# esp32_drone.net
KiCad netlist of a schematic drawn in EAGLE
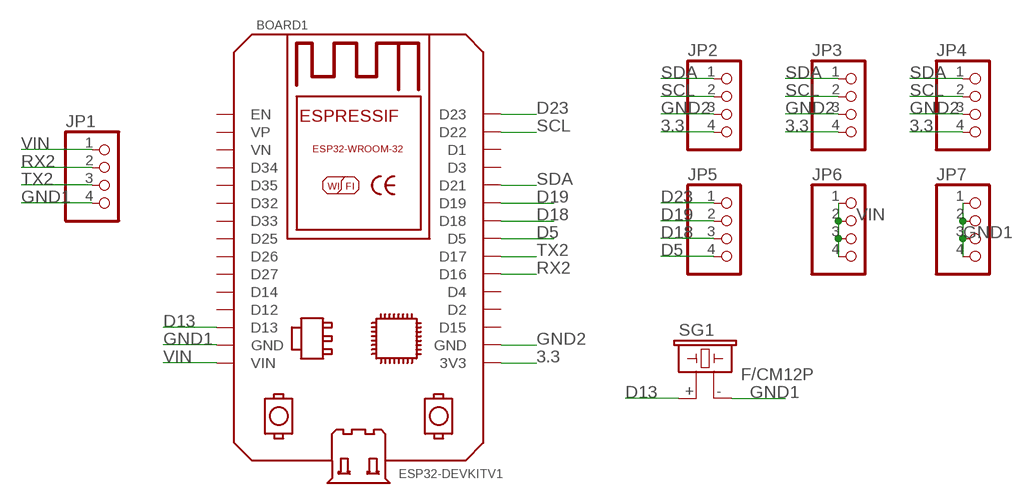
[diagram p0: schematic, sheet 1]

(export (version "E")
  (design (tool "Eeschema 10.0.6"))
  (components
    (comp (ref "BOARD1")
      (value "ESP32DEVKITV1")
      (footprint "eagle-import:ESP32-DEVKITV1")
      (libsource (lib "eagle-import") (part "ESP32DEVKITV1"))
    )
    (comp (ref "JP1")
      (value "PINHD-1X4")
      (footprint "eagle-import:1X04")
      (libsource (lib "eagle-import") (part "PINHD-1X4"))
    )
    (comp (ref "JP2")
      (value "PINHD-1X4")
      (footprint "eagle-import:1X04")
      (libsource (lib "eagle-import") (part "PINHD-1X4"))
    )
    (comp (ref "JP3")
      (value "PINHD-1X4")
      (footprint "eagle-import:1X04")
      (libsource (lib "eagle-import") (part "PINHD-1X4"))
    )
    (comp (ref "JP4")
      (value "PINHD-1X4")
      (footprint "eagle-import:1X04")
      (libsource (lib "eagle-import") (part "PINHD-1X4"))
    )
    (comp (ref "JP5")
      (value "PINHD-1X4")
      (footprint "eagle-import:1X04")
      (libsource (lib "eagle-import") (part "PINHD-1X4"))
    )
    (comp (ref "JP6")
      (value "PINHD-1X4")
      (footprint "eagle-import:1X04")
      (libsource (lib "eagle-import") (part "PINHD-1X4"))
    )
    (comp (ref "JP7")
      (value "PINHD-1X4")
      (footprint "eagle-import:1X04")
      (libsource (lib "eagle-import") (part "PINHD-1X4"))
    )
    (comp (ref "SG1")
      (value "F/CM12P")
      (footprint "eagle-import:F_CM12P")
      (libsource (lib "eagle-import") (part "F/CM12P"))
    )
  )
  (nets
    (net (code "1") (name "/3.3") (class "Default")
      (node (ref "BOARD1") (pin "3V3") (pinfunction "3V3_3V3") (pintype "bidirectional"))
      (node (ref "JP2") (pin "4") (pinfunction "4_4") (pintype "passive"))
      (node (ref "JP3") (pin "4") (pinfunction "4_4") (pintype "passive"))
      (node (ref "JP4") (pin "4") (pinfunction "4_4") (pintype "passive"))
    )
    (net (code "2") (name "/D5") (class "Default")
      (node (ref "BOARD1") (pin "D5") (pinfunction "D5_D5") (pintype "bidirectional"))
      (node (ref "JP5") (pin "4") (pinfunction "4_4") (pintype "passive"))
    )
    (net (code "3") (name "/D13") (class "Default")
      (node (ref "BOARD1") (pin "D13") (pinfunction "D13_D13") (pintype "bidirectional"))
      (node (ref "SG1") (pin "+") (pinfunction "1_+") (pintype "passive"))
    )
    (net (code "4") (name "/D18") (class "Default")
      (node (ref "BOARD1") (pin "D18") (pinfunction "D18_D18") (pintype "bidirectional"))
      (node (ref "JP5") (pin "3") (pinfunction "3_3") (pintype "passive"))
    )
    (net (code "5") (name "/D19") (class "Default")
      (node (ref "BOARD1") (pin "D19") (pinfunction "D19_D19") (pintype "bidirectional"))
      (node (ref "JP5") (pin "2") (pinfunction "2_2") (pintype "passive"))
    )
    (net (code "6") (name "/D23") (class "Default")
      (node (ref "BOARD1") (pin "D23") (pinfunction "D23_D23") (pintype "bidirectional"))
      (node (ref "JP5") (pin "1") (pinfunction "1_1") (pintype "passive"))
    )
    (net (code "7") (name "/GND1") (class "Default")
      (node (ref "BOARD1") (pin "GND") (pinfunction "GND_GND") (pintype "bidirectional"))
      (node (ref "JP1") (pin "4") (pinfunction "4_4") (pintype "passive"))
      (node (ref "JP7") (pin "1") (pinfunction "1_1") (pintype "passive"))
      (node (ref "JP7") (pin "2") (pinfunction "2_2") (pintype "passive"))
      (node (ref "JP7") (pin "3") (pinfunction "3_3") (pintype "passive"))
      (node (ref "JP7") (pin "4") (pinfunction "4_4") (pintype "passive"))
      (node (ref "SG1") (pin "-") (pinfunction "2_-") (pintype "passive"))
    )
    (net (code "8") (name "/GND2") (class "Default")
      (node (ref "BOARD1") (pin "GND@1") (pinfunction "GND_GND@1") (pintype "bidirectional"))
      (node (ref "JP2") (pin "3") (pinfunction "3_3") (pintype "passive"))
      (node (ref "JP3") (pin "3") (pinfunction "3_3") (pintype "passive"))
      (node (ref "JP4") (pin "3") (pinfunction "3_3") (pintype "passive"))
    )
    (net (code "9") (name "/RX2") (class "Default")
      (node (ref "BOARD1") (pin "D16") (pinfunction "D16_D16") (pintype "bidirectional"))
      (node (ref "JP1") (pin "2") (pinfunction "2_2") (pintype "passive"))
    )
    (net (code "10") (name "/SCL") (class "Default")
      (node (ref "BOARD1") (pin "D22") (pinfunction "D22_D22") (pintype "bidirectional"))
      (node (ref "JP2") (pin "2") (pinfunction "2_2") (pintype "passive"))
      (node (ref "JP3") (pin "2") (pinfunction "2_2") (pintype "passive"))
      (node (ref "JP4") (pin "2") (pinfunction "2_2") (pintype "passive"))
    )
    (net (code "11") (name "/SDA") (class "Default")
      (node (ref "BOARD1") (pin "D21") (pinfunction "D21_D21") (pintype "bidirectional"))
      (node (ref "JP2") (pin "1") (pinfunction "1_1") (pintype "passive"))
      (node (ref "JP3") (pin "1") (pinfunction "1_1") (pintype "passive"))
      (node (ref "JP4") (pin "1") (pinfunction "1_1") (pintype "passive"))
    )
    (net (code "12") (name "/TX2") (class "Default")
      (node (ref "BOARD1") (pin "D17") (pinfunction "D17_D17") (pintype "bidirectional"))
      (node (ref "JP1") (pin "3") (pinfunction "3_3") (pintype "passive"))
    )
    (net (code "13") (name "/VIN") (class "Default")
      (node (ref "BOARD1") (pin "VIN") (pinfunction "VIN_VIN") (pintype "bidirectional"))
      (node (ref "JP1") (pin "1") (pinfunction "1_1") (pintype "passive"))
      (node (ref "JP6") (pin "1") (pinfunction "1_1") (pintype "passive"))
      (node (ref "JP6") (pin "2") (pinfunction "2_2") (pintype "passive"))
      (node (ref "JP6") (pin "3") (pinfunction "3_3") (pintype "passive"))
      (node (ref "JP6") (pin "4") (pinfunction "4_4") (pintype "passive"))
    )
    (net (code "14") (name "unconnected-(BOARD1-PadD1)") (class "Default")
      (node (ref "BOARD1") (pin "D1") (pinfunction "D1_D1") (pintype "bidirectional"))
    )
    (net (code "15") (name "unconnected-(BOARD1-PadD2)") (class "Default")
      (node (ref "BOARD1") (pin "D2") (pinfunction "D2_D2") (pintype "bidirectional"))
    )
    (net (code "16") (name "unconnected-(BOARD1-PadD3)") (class "Default")
      (node (ref "BOARD1") (pin "D3") (pinfunction "D3_D3") (pintype "bidirectional"))
    )
    (net (code "17") (name "unconnected-(BOARD1-PadD4)") (class "Default")
      (node (ref "BOARD1") (pin "D4") (pinfunction "D4_D4") (pintype "bidirectional"))
    )
    (net (code "18") (name "unconnected-(BOARD1-PadD12)") (class "Default")
      (node (ref "BOARD1") (pin "D12") (pinfunction "D12_D12") (pintype "bidirectional"))
    )
    (net (code "19") (name "unconnected-(BOARD1-PadD14)") (class "Default")
      (node (ref "BOARD1") (pin "D14") (pinfunction "D14_D14") (pintype "bidirectional"))
    )
    (net (code "20") (name "unconnected-(BOARD1-PadD15)") (class "Default")
      (node (ref "BOARD1") (pin "D15") (pinfunction "D15_D15") (pintype "bidirectional"))
    )
    (net (code "21") (name "unconnected-(BOARD1-PadD25)") (class "Default")
      (node (ref "BOARD1") (pin "D25") (pinfunction "D25_D25") (pintype "bidirectional"))
    )
    (net (code "22") (name "unconnected-(BOARD1-PadD26)") (class "Default")
      (node (ref "BOARD1") (pin "D26") (pinfunction "D26_D26") (pintype "bidirectional"))
    )
    (net (code "23") (name "unconnected-(BOARD1-PadD27)") (class "Default")
      (node (ref "BOARD1") (pin "D27") (pinfunction "D27_D27") (pintype "bidirectional"))
    )
    (net (code "24") (name "unconnected-(BOARD1-PadD32)") (class "Default")
      (node (ref "BOARD1") (pin "D32") (pinfunction "D32_D32") (pintype "bidirectional"))
    )
    (net (code "25") (name "unconnected-(BOARD1-PadD33)") (class "Default")
      (node (ref "BOARD1") (pin "D33") (pinfunction "D33_D33") (pintype "bidirectional"))
    )
    (net (code "26") (name "unconnected-(BOARD1-PadD34)") (class "Default")
      (node (ref "BOARD1") (pin "D34") (pinfunction "D34_D34") (pintype "bidirectional"))
    )
    (net (code "27") (name "unconnected-(BOARD1-PadD35)") (class "Default")
      (node (ref "BOARD1") (pin "D35") (pinfunction "D35_D35") (pintype "bidirectional"))
    )
    (net (code "28") (name "unconnected-(BOARD1-PadEN)") (class "Default")
      (node (ref "BOARD1") (pin "EN") (pinfunction "EN_EN") (pintype "bidirectional"))
    )
    (net (code "29") (name "unconnected-(BOARD1-PadVN)") (class "Default")
      (node (ref "BOARD1") (pin "VN") (pinfunction "VN_VN") (pintype "bidirectional"))
    )
    (net (code "30") (name "unconnected-(BOARD1-PadVP)") (class "Default")
      (node (ref "BOARD1") (pin "VP") (pinfunction "VP_VP") (pintype "bidirectional"))
    )
  )
)
